# 3_6_1--esp32_-_0604.net
KiCad netlist of a schematic drawn in EasyEDA Pro
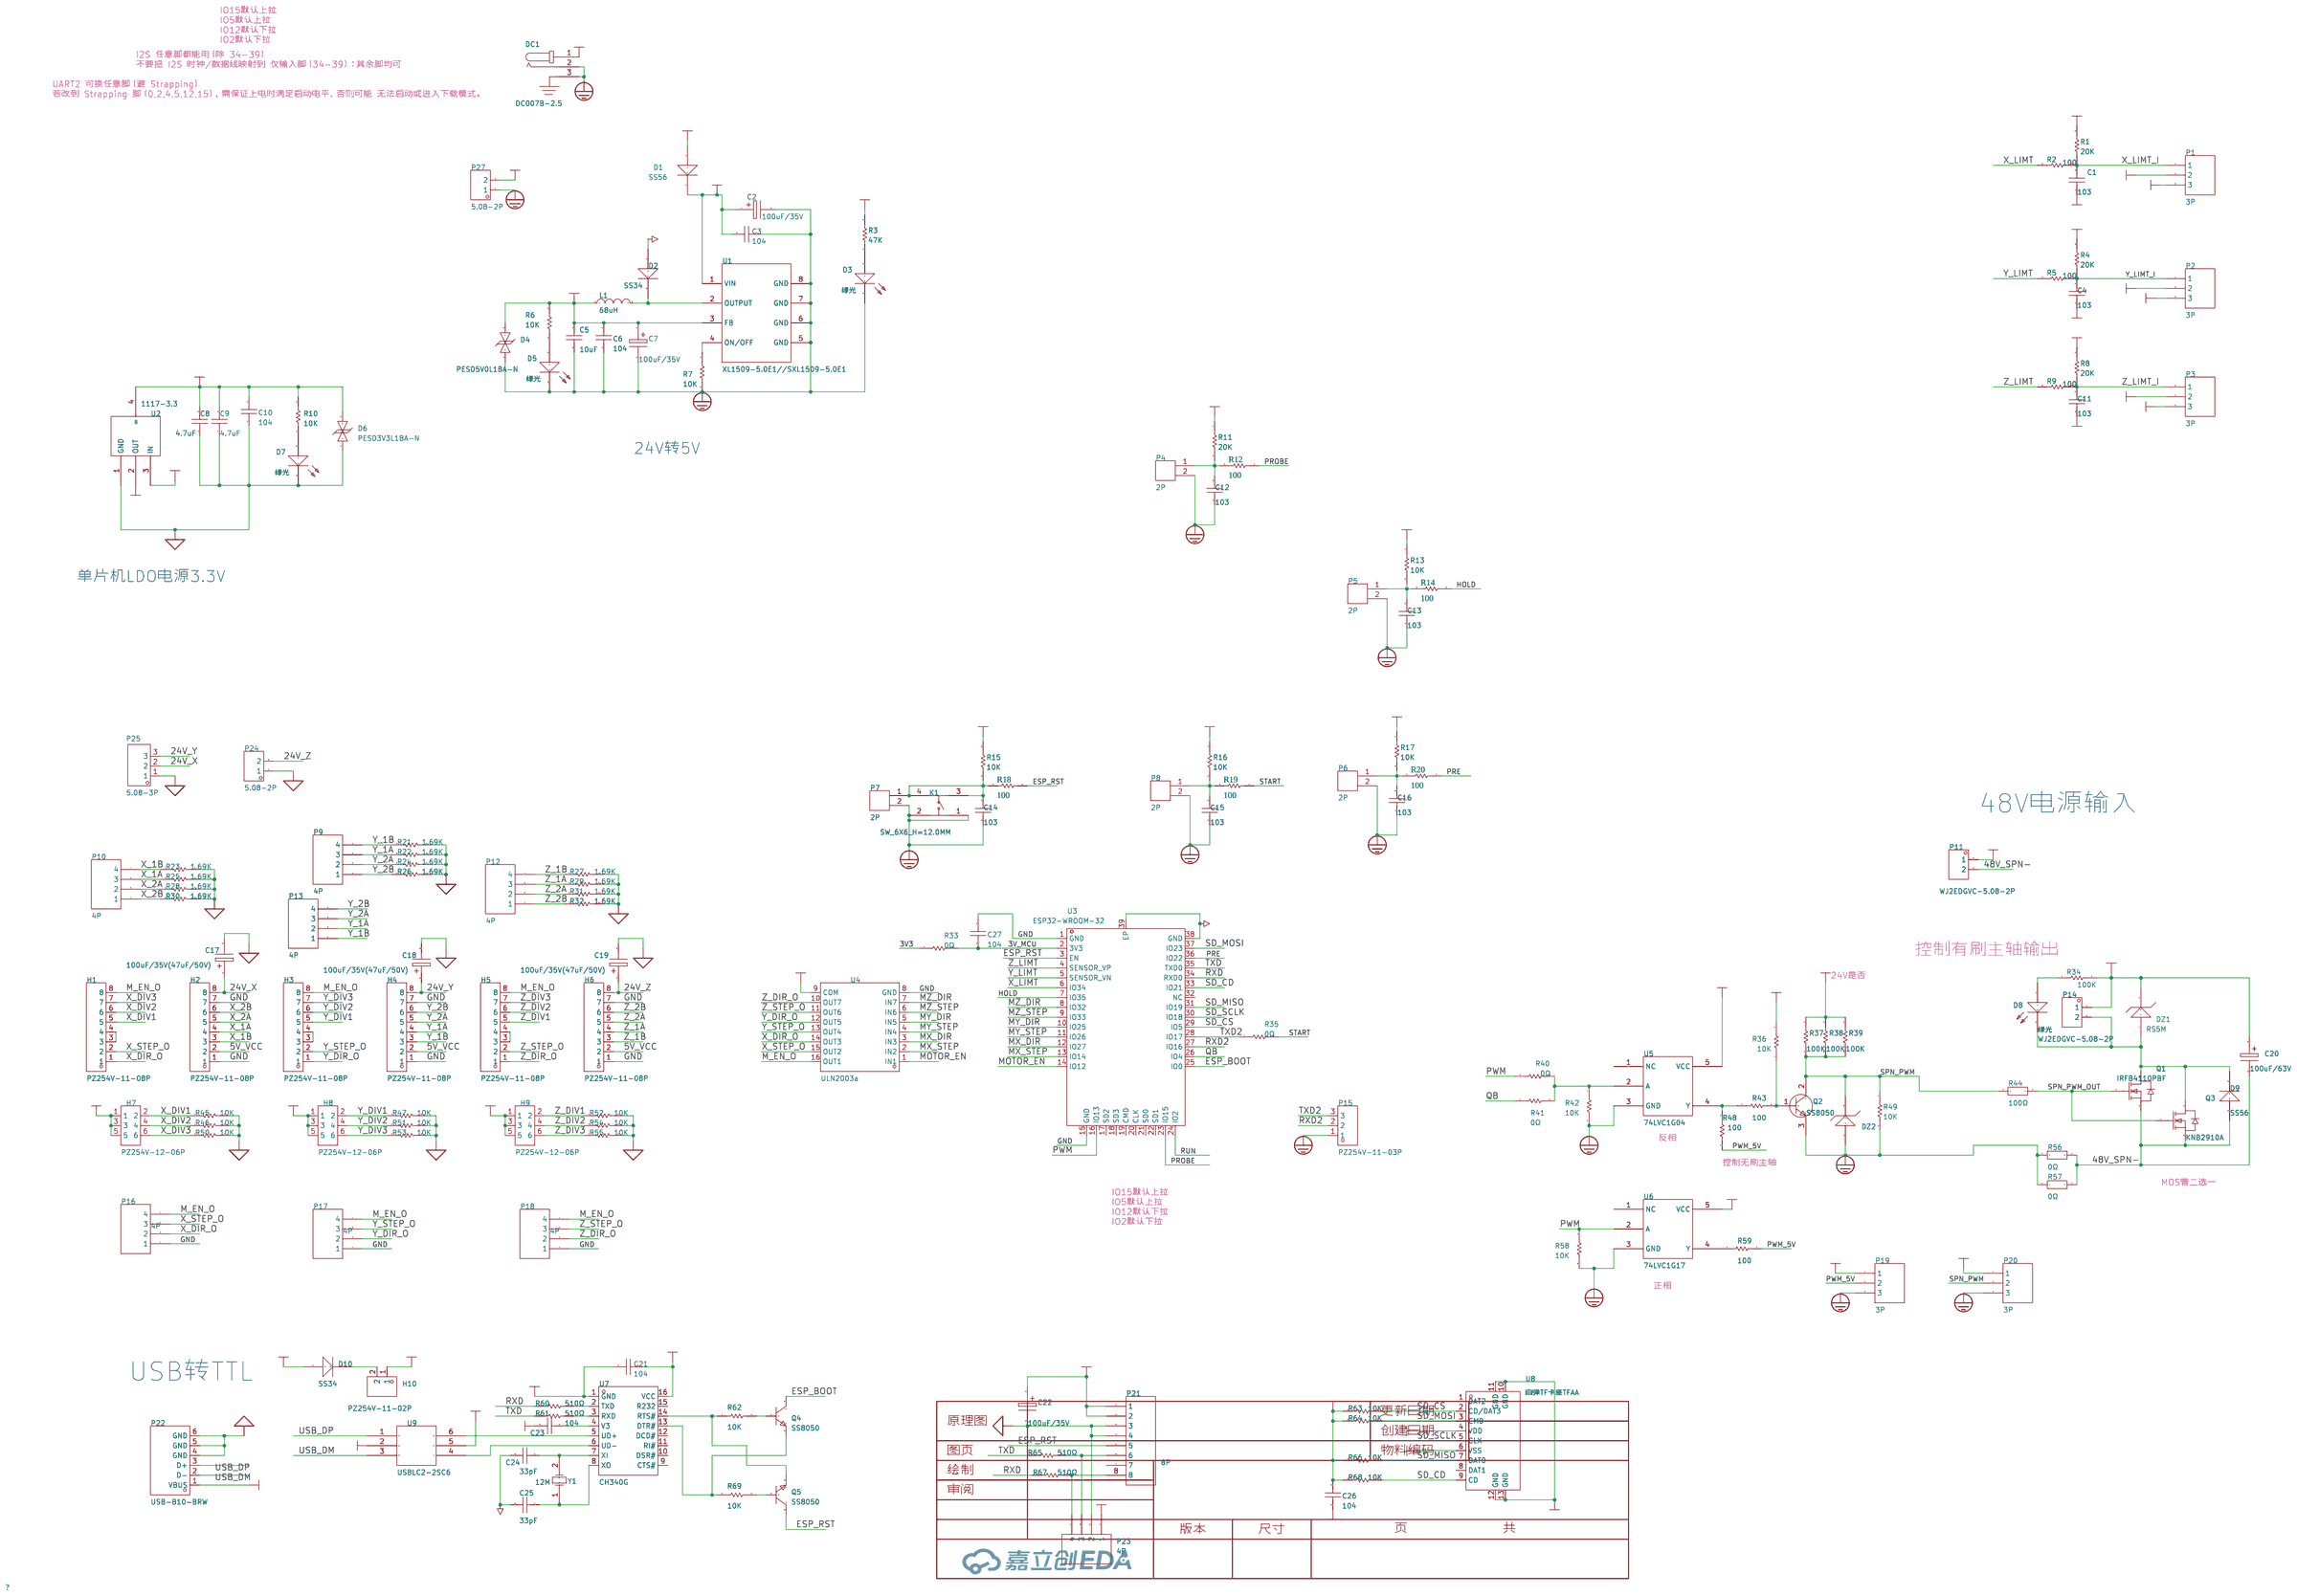
[diagram p0: schematic sheet]

(export (version "E")
  (design (tool "Eeschema 10.0.6"))
  (components
    (comp (ref "C1") (value "103") (footprint "easyedapro:11") (libsource (lib "easyedapro") (part "CAP")))
    (comp (ref "C2")
      (value "100uF/35V")
      (footprint "easyedapro:电解电容贴片10x10")
      (libsource (lib "easyedapro") (part "ELECTRO1"))
    )
    (comp (ref "C3")
      (value "104")
      (footprint "easyedapro:0603C")
      (description "Capacitor (Semiconductor SIM Model)")
      (libsource (lib "easyedapro") (part "Cap Semi"))
    )
    (comp (ref "C4") (value "103") (footprint "easyedapro:11") (libsource (lib "easyedapro") (part "CAP")))
    (comp (ref "C5") (value "10uF") (libsource (lib "") (part "CAP_1")))
    (comp (ref "C6")
      (value "104")
      (footprint "easyedapro:0603C")
      (description "Capacitor (Semiconductor SIM Model)")
      (libsource (lib "easyedapro") (part "Cap Semi"))
    )
    (comp (ref "C7")
      (value "100uF/35V")
      (footprint "easyedapro:0603C")
      (libsource (lib "easyedapro") (part "ELECTRO1"))
    )
    (comp (ref "C8") (value "4.7uF") (libsource (lib "") (part "CAP_1")))
    (comp (ref "C9") (value "4.7uF") (libsource (lib "") (part "CAP_1")))
    (comp (ref "C10")
      (value "104")
      (footprint "easyedapro:0603C")
      (description "Capacitor (Semiconductor SIM Model)")
      (libsource (lib "easyedapro") (part "Cap Semi"))
    )
    (comp (ref "C11") (value "103") (footprint "easyedapro:11") (libsource (lib "easyedapro") (part "CAP")))
    (comp (ref "C12") (value "103") (footprint "easyedapro:11") (libsource (lib "easyedapro") (part "CAP")))
    (comp (ref "C13") (value "103") (footprint "easyedapro:11") (libsource (lib "easyedapro") (part "CAP")))
    (comp (ref "C14") (value "103") (footprint "easyedapro:11") (libsource (lib "easyedapro") (part "CAP")))
    (comp (ref "C15") (value "103") (footprint "easyedapro:11") (libsource (lib "easyedapro") (part "CAP")))
    (comp (ref "C16") (value "103") (footprint "easyedapro:11") (libsource (lib "easyedapro") (part "CAP")))
    (comp (ref "C17")
      (value "100uF/35V(47uF/50V)")
      (footprint "easyedapro:电解电容贴片10x10")
      (libsource (lib "easyedapro") (part "ELECTRO1"))
    )
    (comp (ref "C18")
      (value "100uF/35V(47uF/50V)")
      (footprint "easyedapro:电解电容贴片10x10")
      (libsource (lib "easyedapro") (part "ELECTRO1"))
    )
    (comp (ref "C19")
      (value "100uF/35V(47uF/50V)")
      (footprint "easyedapro:电解电容贴片10x10")
      (libsource (lib "easyedapro") (part "ELECTRO1"))
    )
    (comp (ref "C20")
      (value "100uF/63V")
      (footprint "easyedapro:电解电容贴片10x10")
      (libsource (lib "easyedapro") (part "ELECTRO1"))
    )
    (comp (ref "C21")
      (value "104")
      (footprint "easyedapro:0603C")
      (description "Capacitor (Semiconductor SIM Model)")
      (libsource (lib "easyedapro") (part "Cap Semi"))
    )
    (comp (ref "C22")
      (value "100uF/35V")
      (footprint "easyedapro:电解电容贴片10x10")
      (libsource (lib "easyedapro") (part "ELECTRO1"))
    )
    (comp (ref "C23")
      (value "104")
      (footprint "easyedapro:0603C")
      (description "Capacitor (Semiconductor SIM Model)")
      (libsource (lib "easyedapro") (part "Cap Semi"))
    )
    (comp (ref "C24")
      (value "18pF")
      (footprint "easyedapro:0603C")
      (description "Capacitor (Semiconductor SIM Model)")
      (libsource (lib "easyedapro") (part "Cap Semi"))
    )
    (comp (ref "C25")
      (value "18pF")
      (footprint "easyedapro:0603C")
      (description "Capacitor (Semiconductor SIM Model)")
      (libsource (lib "easyedapro") (part "Cap Semi"))
    )
    (comp (ref "C26")
      (value "104")
      (footprint "easyedapro:11")
      (description "Capacitor (Semiconductor SIM Model)")
      (libsource (lib "easyedapro") (part "Cap Semi"))
    )
    (comp (ref "C27")
      (value "104")
      (footprint "easyedapro:0603C")
      (description "Capacitor (Semiconductor SIM Model)")
      (libsource (lib "easyedapro") (part "Cap Semi"))
    )
    (comp (ref "D1") (value "SS56") (footprint "easyedapro:SMA") (libsource (lib "") (part "1N4148_1")))
    (comp (ref "D2") (value "SS34") (libsource (lib "easyedapro") (part "1N4148")))
    (comp (ref "D3")
      (value "绿光")
      (footprint "easyedapro:0603LED")
      (libsource (lib "easyedapro") (part "LED"))
    )
    (comp (ref "D4")
      (value "PESD5V0L1BA-N")
      (footprint "easyedapro:SOD-523_L1.2-W0.8-LS1.6-BI")
      (description "极性:Bidirectional;反向关断电压（典型值）:5V (Max);击穿电压（最小值）:6V;箝位电压:15V;峰值脉冲电流（10/1000us）:5A (8/20us);")
      (fields (field (name "Manufacturer") "BORN伯恩半导体"))
      (libsource (lib "easyedapro") (part "PESD5V0S1BBN"))
    )
    (comp (ref "D5")
      (value "绿光")
      (footprint "easyedapro:0603LED")
      (libsource (lib "easyedapro") (part "LED"))
    )
    (comp (ref "D6")
      (value "PESD3V3L1BA-N")
      (footprint "easyedapro:SOD-523_L1.2-W0.8-LS1.6-BI")
      (description "极性:Bidirectional;反向关断电压（典型值）:5V (Max);击穿电压（最小值）:6V;箝位电压:15V;峰值脉冲电流（10/1000us）:5A (8/20us);")
      (fields (field (name "Manufacturer") "BORN伯恩半导体"))
      (libsource (lib "easyedapro") (part "PESD5V0S1BBN"))
    )
    (comp (ref "D7")
      (value "绿光")
      (footprint "easyedapro:0603LED")
      (libsource (lib "easyedapro") (part "LED"))
    )
    (comp (ref "D8")
      (value "绿光")
      (footprint "easyedapro:0603LED")
      (libsource (lib "easyedapro") (part "LED"))
    )
    (comp (ref "D9") (value "SS56") (libsource (lib "easyedapro") (part "1N4148")))
    (comp (ref "D10") (value "SS34") (footprint "easyedapro:SMA") (libsource (lib "") (part "1N4148_1")))
    (comp (ref "DC1")
      (value "DC007B-2.5")
      (footprint "easyedapro:DC-IN-TH_HX-DC007B-2.5")
      (description "连接器类型:DC电源插座;安装方式:弯插;触点内径:2.5mm;触点外径:7.7mm;额定电流:5A;额定电压:20V;工作温度:-25°C~+70°C;")
      (fields (field (name "Manufacturer") "SHOU HAN(首韩)"))
      (libsource (lib "easyedapro") (part "DC007B-2.5"))
    )
    (comp (ref "DZ1") (value "RS5M") (libsource (lib "easyedapro") (part "ѹ")))
    (comp (ref "DZ2") (value "--ѹ------SMAZ10V") (libsource (lib "easyedapro") (part "ѹ")))
    (comp (ref "H1")
      (value "PZ254V-11-08P")
      (footprint "easyedapro:HDR-TH_8P-P2.54-V-M")
      (fields (field (name "Manufacturer") "XFCN(兴飞)"))
      (libsource (lib "easyedapro") (part "PZ254V-11-08P"))
    )
    (comp (ref "H2")
      (value "PZ254V-11-08P")
      (footprint "easyedapro:HDR-TH_8P-P2.54-V-M")
      (fields (field (name "Manufacturer") "XFCN(兴飞)"))
      (libsource (lib "easyedapro") (part "PZ254V-11-08P"))
    )
    (comp (ref "H3")
      (value "PZ254V-11-08P")
      (footprint "easyedapro:HDR-TH_8P-P2.54-V-M")
      (fields (field (name "Manufacturer") "XFCN(兴飞)"))
      (libsource (lib "easyedapro") (part "PZ254V-11-08P"))
    )
    (comp (ref "H4")
      (value "PZ254V-11-08P")
      (footprint "easyedapro:HDR-TH_8P-P2.54-V-M")
      (fields (field (name "Manufacturer") "XFCN(兴飞)"))
      (libsource (lib "easyedapro") (part "PZ254V-11-08P"))
    )
    (comp (ref "H5")
      (value "PZ254V-11-08P")
      (footprint "easyedapro:HDR-TH_8P-P2.54-V-M")
      (fields (field (name "Manufacturer") "XFCN(兴飞)"))
      (libsource (lib "easyedapro") (part "PZ254V-11-08P"))
    )
    (comp (ref "H6")
      (value "PZ254V-11-08P")
      (footprint "easyedapro:HDR-TH_8P-P2.54-V-M")
      (fields (field (name "Manufacturer") "XFCN(兴飞)"))
      (libsource (lib "easyedapro") (part "PZ254V-11-08P"))
    )
    (comp (ref "H7")
      (value "PZ254V-12-06P")
      (footprint "easyedapro:HDR-TH_PZ254V-12-06P-A40")
      (description "排针2.54mm间距 直插 2x03位 直针外露4mm")
      (fields (field (name "Manufacturer") "XFCN(兴飞)"))
      (libsource (lib "easyedapro") (part "PZ254V-12-06P-A40"))
    )
    (comp (ref "H8")
      (value "PZ254V-12-06P")
      (footprint "easyedapro:HDR-TH_PZ254V-12-06P-A40")
      (description "排针2.54mm间距 直插 2x03位 直针外露4mm")
      (fields (field (name "Manufacturer") "XFCN(兴飞)"))
      (libsource (lib "easyedapro") (part "PZ254V-12-06P-A40"))
    )
    (comp (ref "H9")
      (value "PZ254V-12-06P")
      (footprint "easyedapro:HDR-TH_PZ254V-12-06P-A40")
      (description "排针2.54mm间距 直插 2x03位 直针外露4mm")
      (fields (field (name "Manufacturer") "XFCN(兴飞)"))
      (libsource (lib "easyedapro") (part "PZ254V-12-06P-A40"))
    )
    (comp (ref "H10")
      (value "PZ254V-11-02P")
      (footprint "easyedapro:HDR-TH_2P-P2.54-V-M")
      (fields (field (name "Manufacturer") "XFCN(兴飞)"))
      (libsource (lib "easyedapro") (part "PZ254V-11-02P"))
    )
    (comp (ref "K1")
      (value "SW_6X6_H=12.0MM")
      (footprint "easyedapro:KEY-SMD_4P-L6.0-W6.0-P4.50-LS9.0")
      (libsource (lib "easyedapro") (part "SW_6X6_H=12.0MM"))
    )
    (comp (ref "L1")
      (value "68uH")
      (footprint "easyedapro:IND-SMD_L7.0-W7.0_SMDRI74-330MT")
      (description "电感值:33uH;精度:±20%;额定电流:960mA;饱和电流(Isat):1.8A;类型:屏蔽电感;")
      (fields (field (name "Manufacturer Part") "SMDRI74-330MT") (field (name "Manufacturer") "SXN(顺翔诺)"))
      (libsource (lib "easyedapro") (part "SMDRI74-330MT"))
    )
    (comp (ref "P1")
      (value "3P")
      (footprint "easyedapro:HDR1X3_CON")
      (libsource (lib "easyedapro") (part "3P"))
    )
    (comp (ref "P2")
      (value "3P")
      (footprint "easyedapro:HDR1X3_CON")
      (libsource (lib "easyedapro") (part "3P"))
    )
    (comp (ref "P3")
      (value "3P")
      (footprint "easyedapro:HDR1X3_CON")
      (libsource (lib "easyedapro") (part "3P"))
    )
    (comp (ref "P4") (value "2P") (libsource (lib "easyedapro") (part "2P")))
    (comp (ref "P5") (value "2P") (libsource (lib "easyedapro") (part "2P")))
    (comp (ref "P6") (value "2P") (libsource (lib "easyedapro") (part "2P")))
    (comp (ref "P7") (value "2P") (libsource (lib "easyedapro") (part "2P")))
    (comp (ref "P8") (value "2P") (libsource (lib "easyedapro") (part "2P")))
    (comp (ref "P9") (value "4P") (footprint "easyedapro:HDR1X4_CON") (libsource (lib "") (part "4P_1")))
    (comp (ref "P10") (value "4P") (footprint "easyedapro:HDR1X4_CON") (libsource (lib "") (part "4P_1")))
    (comp (ref "P11")
      (value "WJ2EDGVC-5.08-2P")
      (footprint "easyedapro:CONN-TH_WJ2EDGVC-5.08-2P")
      (fields (field (name "Manufacturer") "KANGNEX(康奈克斯电气)"))
      (libsource (lib "easyedapro") (part "WJ2EDGVC-5.08-2P"))
    )
    (comp (ref "P12") (value "4P") (footprint "easyedapro:HDR1X4_CON") (libsource (lib "") (part "4P_1")))
    (comp (ref "P13") (value "4P") (footprint "easyedapro:HDR1X4_CON") (libsource (lib "") (part "4P_1")))
    (comp (ref "P14")
      (value "WJ2EDGVC-5.08-2P")
      (footprint "easyedapro:CONN-TH_WJ2EDGVC-5.08-2P")
      (fields (field (name "Manufacturer") "KANGNEX(康奈克斯电气)"))
      (libsource (lib "easyedapro") (part "WJ2EDGVC-5.08-2P"))
    )
    (comp (ref "P15")
      (value "PZ254V-11-03P")
      (footprint "easyedapro:HDR-TH_3P-P2.54-V-M")
      (fields (field (name "Manufacturer") "XFCN(兴飞)"))
      (libsource (lib "easyedapro") (part "PZ254V-11-03P_C2937625"))
    )
    (comp (ref "P16") (value "4P") (libsource (lib "easyedapro") (part "4P")))
    (comp (ref "P17") (value "4P") (libsource (lib "easyedapro") (part "4P")))
    (comp (ref "P18") (value "4P") (libsource (lib "easyedapro") (part "4P")))
    (comp (ref "P19")
      (value "3P")
      (footprint "easyedapro:HDR1X3_CON")
      (libsource (lib "easyedapro") (part "3P"))
    )
    (comp (ref "P20")
      (value "3P")
      (footprint "easyedapro:HDR1X3_CON")
      (libsource (lib "easyedapro") (part "3P"))
    )
    (comp (ref "P21") (value "8P") (footprint "easyedapro:IDC8") (libsource (lib "easyedapro") (part "8P")))
    (comp (ref "P22")
      (value "USB-B10-BRW")
      (footprint "easyedapro:USB-B-TH_USB-B10-BRW")
      (fields (field (name "Manufacturer") "XUNPU(讯普)"))
      (libsource (lib "easyedapro") (part "USB-B10-BRW"))
    )
    (comp (ref "P23") (value "4P") (footprint "easyedapro:HDR1X4_CON") (libsource (lib "") (part "4P_1")))
    (comp (ref "P24")
      (value "5.08-2P")
      (footprint "easyedapro:CONN-TH_WJ2EDGVC-5.08-2P")
      (fields (field (name "Manufacturer") "KANGNEX(康奈克斯电气)"))
      (libsource (lib "easyedapro") (part "WJ2EDGVC-5.08-2P"))
    )
    (comp (ref "P25")
      (value "5.08-3P")
      (footprint "easyedapro:CONN-TH_3P-P5.08-WJ2EDGVC-3P")
      (description "连接器类型:板端/插座-闭口;间距:5.08mm;排数:1;每排PIN数:3;安装方式:直针;颜色:绿色;")
      (fields (field (name "Manufacturer") "KANGNEX(康奈克斯电气)"))
      (libsource (lib "easyedapro") (part "WJ2EDGVC-3P"))
    )
    (comp (ref "P27")
      (value "5.08-2P")
      (footprint "easyedapro:CONN-TH_WJ2EDGVC-5.08-2P")
      (fields (field (name "Manufacturer") "KANGNEX(康奈克斯电气)"))
      (libsource (lib "easyedapro") (part "WJ2EDGVC-5.08-2P"))
    )
    (comp (ref "Q1")
      (value "IRFB4110PBF")
      (footprint "easyedapro:TO-220-3_L10.0-W4.5-P2.54-L")
      (fields (field (name "Manufacturer") "Infineon(英飞凌)"))
      (libsource (lib "easyedapro") (part "IRFB4110PBF"))
    )
    (comp (ref "Q2")
      (value "SS8050")
      (fields (field (name "Publisher") "Altium Limited"))
      (libsource (lib "easyedapro") (part "NPN"))
    )
    (comp (ref "Q3")
      (value "KNB2910A")
      (footprint "easyedapro:TO-263-2_L10.0-W9.1-P5.08-LS15.2-TL")
      (description "类型:-;漏源电压(Vdss):100V;连续漏极电流(Id):130A;导通电阻(RDS(on)):9mΩ@70V,10A;耗散功率(Pd):300W;阈值电压(Vgs(th)):4V;")
      (fields (field (name "Manufacturer") "KIA"))
      (libsource (lib "easyedapro") (part "KNB2910A"))
    )
    (comp (ref "Q4")
      (value "SS8050")
      (footprint "easyedapro:SOT-23-3_L2.9-W1.3-P1.90-LS2.4-BR")
      (fields (field (name "Manufacturer") "Doeshare(德芯)"))
      (libsource (lib "easyedapro") (part "SS8050_C2931717"))
    )
    (comp (ref "Q5")
      (value "SS8050")
      (footprint "easyedapro:SOT-23-3_L2.9-W1.3-P1.90-LS2.4-BR")
      (fields (field (name "Manufacturer") "Doeshare(德芯)"))
      (libsource (lib "easyedapro") (part "SS8050_C2931717"))
    )
    (comp (ref "R1")
      (value "20K")
      (footprint "easyedapro:10")
      (description "Resistor")
      (libsource (lib "easyedapro") (part "RES"))
    )
    (comp (ref "R2")
      (value "100")
      (footprint "easyedapro:10")
      (description "Resistor")
      (libsource (lib "easyedapro") (part "RES"))
    )
    (comp (ref "R3")
      (value "47K")
      (footprint "easyedapro:0603R")
      (description "Resistor")
      (libsource (lib "easyedapro") (part "RES"))
    )
    (comp (ref "R4")
      (value "20K")
      (footprint "easyedapro:10")
      (description "Resistor")
      (libsource (lib "easyedapro") (part "RES"))
    )
    (comp (ref "R5")
      (value "100")
      (footprint "easyedapro:10")
      (description "Resistor")
      (libsource (lib "easyedapro") (part "RES"))
    )
    (comp (ref "R6")
      (value "10K")
      (footprint "easyedapro:0603R")
      (description "Resistor")
      (libsource (lib "easyedapro") (part "RES"))
    )
    (comp (ref "R7")
      (value "10K")
      (footprint "easyedapro:0603R")
      (description "Resistor")
      (libsource (lib "easyedapro") (part "RES"))
    )
    (comp (ref "R8")
      (value "20K")
      (footprint "easyedapro:10")
      (description "Resistor")
      (libsource (lib "easyedapro") (part "RES"))
    )
    (comp (ref "R9")
      (value "100")
      (footprint "easyedapro:10")
      (description "Resistor")
      (libsource (lib "easyedapro") (part "RES"))
    )
    (comp (ref "R10")
      (value "10K")
      (footprint "easyedapro:0603R")
      (description "Resistor")
      (libsource (lib "easyedapro") (part "RES"))
    )
    (comp (ref "R11")
      (value "10K")
      (footprint "easyedapro:0603R")
      (description "Resistor")
      (libsource (lib "easyedapro") (part "RES"))
    )
    (comp (ref "R12")
      (value "100")
      (description "Resistor")
      (fields (field (name "Publisher") "Altium Limited"))
      (libsource (lib "") (part "RES_1"))
    )
    (comp (ref "R13")
      (value "10K")
      (footprint "easyedapro:0603R")
      (description "Resistor")
      (libsource (lib "easyedapro") (part "RES"))
    )
    (comp (ref "R14")
      (value "100")
      (description "Resistor")
      (fields (field (name "Publisher") "Altium Limited"))
      (libsource (lib "") (part "RES_1"))
    )
    (comp (ref "R15")
      (value "10K")
      (footprint "easyedapro:0603R")
      (description "Resistor")
      (libsource (lib "easyedapro") (part "RES"))
    )
    (comp (ref "R16")
      (value "10K")
      (footprint "easyedapro:0603R")
      (description "Resistor")
      (libsource (lib "easyedapro") (part "RES"))
    )
    (comp (ref "R17")
      (value "10K")
      (footprint "easyedapro:0603R")
      (description "Resistor")
      (libsource (lib "easyedapro") (part "RES"))
    )
    (comp (ref "R18")
      (value "100")
      (description "Resistor")
      (fields (field (name "Publisher") "Altium Limited"))
      (libsource (lib "") (part "RES_1"))
    )
    (comp (ref "R19")
      (value "100")
      (description "Resistor")
      (fields (field (name "Publisher") "Altium Limited"))
      (libsource (lib "") (part "RES_1"))
    )
    (comp (ref "R20")
      (value "100")
      (description "Resistor")
      (fields (field (name "Publisher") "Altium Limited"))
      (libsource (lib "") (part "RES_1"))
    )
    (comp (ref "R21")
      (value "10K")
      (footprint "easyedapro:0603R")
      (description "Resistor")
      (libsource (lib "easyedapro") (part "10K"))
    )
    (comp (ref "R22")
      (value "10K")
      (footprint "easyedapro:0603R")
      (description "Resistor")
      (libsource (lib "easyedapro") (part "10K"))
    )
    (comp (ref "R23")
      (value "10K")
      (footprint "easyedapro:0603R")
      (description "Resistor")
      (libsource (lib "easyedapro") (part "10K"))
    )
    (comp (ref "R24")
      (value "10K")
      (footprint "easyedapro:0603R")
      (description "Resistor")
      (libsource (lib "easyedapro") (part "10K"))
    )
    (comp (ref "R25")
      (value "10K")
      (footprint "easyedapro:0603R")
      (description "Resistor")
      (libsource (lib "easyedapro") (part "10K"))
    )
    (comp (ref "R26")
      (value "10K")
      (footprint "easyedapro:0603R")
      (description "Resistor")
      (libsource (lib "easyedapro") (part "10K"))
    )
    (comp (ref "R27")
      (value "10K")
      (footprint "easyedapro:0603R")
      (description "Resistor")
      (libsource (lib "easyedapro") (part "10K"))
    )
    (comp (ref "R28")
      (value "10K")
      (footprint "easyedapro:0603R")
      (description "Resistor")
      (libsource (lib "easyedapro") (part "10K"))
    )
    (comp (ref "R29")
      (value "10K")
      (footprint "easyedapro:0603R")
      (description "Resistor")
      (libsource (lib "easyedapro") (part "10K"))
    )
    (comp (ref "R30")
      (value "10K")
      (footprint "easyedapro:0603R")
      (description "Resistor")
      (libsource (lib "easyedapro") (part "10K"))
    )
    (comp (ref "R31")
      (value "10K")
      (footprint "easyedapro:0603R")
      (description "Resistor")
      (libsource (lib "easyedapro") (part "10K"))
    )
    (comp (ref "R32")
      (value "10K")
      (footprint "easyedapro:0603R")
      (description "Resistor")
      (libsource (lib "easyedapro") (part "10K"))
    )
    (comp (ref "R33")
      (value "0Ω")
      (description "Resistor")
      (fields (field (name "Publisher") "Altium Limited"))
      (libsource (lib "") (part "RES_1"))
    )
    (comp (ref "R34")
      (value "100K")
      (description "Resistor")
      (fields (field (name "Publisher") "Altium Limited"))
      (libsource (lib "") (part "RES_1"))
    )
    (comp (ref "R35")
      (value "0Ω")
      (description "Resistor")
      (fields (field (name "Publisher") "Altium Limited"))
      (libsource (lib "") (part "RES_1"))
    )
    (comp (ref "R36")
      (value "10K")
      (description "Resistor")
      (fields (field (name "Publisher") "Altium Limited"))
      (libsource (lib "") (part "RES_1"))
    )
    (comp (ref "R37")
      (value "100K")
      (description "Resistor")
      (fields (field (name "Publisher") "Altium Limited"))
      (libsource (lib "") (part "RES_1"))
    )
    (comp (ref "R38")
      (value "100K")
      (description "Resistor")
      (fields (field (name "Publisher") "Altium Limited"))
      (libsource (lib "") (part "RES_1"))
    )
    (comp (ref "R39")
      (value "100K")
      (description "Resistor")
      (fields (field (name "Publisher") "Altium Limited"))
      (libsource (lib "") (part "RES_1"))
    )
    (comp (ref "R40")
      (value "0Ω")
      (description "Resistor")
      (fields (field (name "Publisher") "Altium Limited"))
      (libsource (lib "") (part "RES_1"))
    )
    (comp (ref "R41")
      (value "0Ω")
      (description "Resistor")
      (fields (field (name "Publisher") "Altium Limited"))
      (libsource (lib "") (part "RES_1"))
    )
    (comp (ref "R42")
      (value "10K")
      (description "Resistor")
      (fields (field (name "Publisher") "Altium Limited"))
      (libsource (lib "") (part "RES_1"))
    )
    (comp (ref "R43")
      (value "100")
      (description "Resistor")
      (fields (field (name "Publisher") "Altium Limited"))
      (libsource (lib "") (part "RES_1"))
    )
    (comp (ref "R44")
      (value "100Ω")
      (footprint "easyedapro:R1210")
      (libsource (lib "easyedapro") (part "电阻"))
    )
    (comp (ref "R45")
      (value "10K")
      (footprint "easyedapro:0603R")
      (description "Resistor")
      (libsource (lib "easyedapro") (part "10K"))
    )
    (comp (ref "R46")
      (value "10K")
      (footprint "easyedapro:0603R")
      (description "Resistor")
      (libsource (lib "easyedapro") (part "10K"))
    )
    (comp (ref "R47")
      (value "10K")
      (footprint "easyedapro:0603R")
      (description "Resistor")
      (libsource (lib "easyedapro") (part "10K"))
    )
    (comp (ref "R48")
      (value "100")
      (description "Resistor")
      (fields (field (name "Publisher") "Altium Limited"))
      (libsource (lib "") (part "RES_1"))
    )
    (comp (ref "R49")
      (value "10K")
      (description "Resistor")
      (fields (field (name "Publisher") "Altium Limited"))
      (libsource (lib "") (part "RES_1"))
    )
    (comp (ref "R50")
      (value "10K")
      (footprint "easyedapro:0603R")
      (description "Resistor")
      (libsource (lib "easyedapro") (part "10K"))
    )
    (comp (ref "R51")
      (value "10K")
      (footprint "easyedapro:0603R")
      (description "Resistor")
      (libsource (lib "easyedapro") (part "10K"))
    )
    (comp (ref "R52")
      (value "10K")
      (footprint "easyedapro:0603R")
      (description "Resistor")
      (libsource (lib "easyedapro") (part "10K"))
    )
    (comp (ref "R53")
      (value "10K")
      (footprint "easyedapro:0603R")
      (description "Resistor")
      (libsource (lib "easyedapro") (part "10K"))
    )
    (comp (ref "R54")
      (value "10K")
      (footprint "easyedapro:0603R")
      (description "Resistor")
      (libsource (lib "easyedapro") (part "10K"))
    )
    (comp (ref "R55")
      (value "10K")
      (footprint "easyedapro:0603R")
      (description "Resistor")
      (libsource (lib "easyedapro") (part "10K"))
    )
    (comp (ref "R56") (value "0Ω") (footprint "easyedapro:R1210") (libsource (lib "easyedapro") (part "电阻")))
    (comp (ref "R57") (value "0Ω") (footprint "easyedapro:R1210") (libsource (lib "easyedapro") (part "电阻")))
    (comp (ref "R58")
      (value "10K")
      (description "Resistor")
      (fields (field (name "Publisher") "Altium Limited"))
      (libsource (lib "") (part "RES_1"))
    )
    (comp (ref "R59")
      (value "100")
      (description "Resistor")
      (fields (field (name "Publisher") "Altium Limited"))
      (libsource (lib "") (part "RES_1"))
    )
    (comp (ref "R60")
      (value "510Ω")
      (footprint "easyedapro:0603R")
      (description "Resistor")
      (libsource (lib "easyedapro") (part "RES"))
    )
    (comp (ref "R61")
      (value "510Ω")
      (footprint "easyedapro:0603R")
      (description "Resistor")
      (libsource (lib "easyedapro") (part "RES"))
    )
    (comp (ref "R62")
      (value "10K")
      (footprint "easyedapro:0603R")
      (description "Resistor")
      (libsource (lib "easyedapro") (part "RES"))
    )
    (comp (ref "R63")
      (value "10K")
      (footprint "easyedapro:10")
      (description "Resistor")
      (libsource (lib "easyedapro") (part "RES"))
    )
    (comp (ref "R64")
      (value "10K")
      (footprint "easyedapro:10")
      (description "Resistor")
      (libsource (lib "easyedapro") (part "RES"))
    )
    (comp (ref "R65")
      (value "510Ω")
      (footprint "easyedapro:0603R")
      (description "Resistor")
      (libsource (lib "easyedapro") (part "RES"))
    )
    (comp (ref "R66")
      (value "10K")
      (footprint "easyedapro:10")
      (description "Resistor")
      (libsource (lib "easyedapro") (part "RES"))
    )
    (comp (ref "R67")
      (value "510Ω")
      (footprint "easyedapro:0603R")
      (description "Resistor")
      (libsource (lib "easyedapro") (part "RES"))
    )
    (comp (ref "R68")
      (value "10K")
      (footprint "easyedapro:10")
      (description "Resistor")
      (libsource (lib "easyedapro") (part "RES"))
    )
    (comp (ref "R69")
      (value "10K")
      (footprint "easyedapro:0603R")
      (description "Resistor")
      (libsource (lib "easyedapro") (part "RES"))
    )
    (comp (ref "U1")
      (value "XL1509-5.0E1//SXL1509-5.0E1")
      (footprint "easyedapro:SOIC-8_L5.0-W4.0-P1.27-LS6.0-BL")
      (description "功能类型:降压型;同步整流:-;输出通道数:-;拓扑结构:-;输入电压:-;输出电流(最大值):-;开关频率:-;")
      (fields (field (name "Manufacturer") "XLSEMI(芯龙)"))
      (libsource (lib "easyedapro") (part "XL1509-5.0E1"))
    )
    (comp (ref "U2")
      (value "1117-3.3")
      (footprint "easyedapro:SOT-223")
      (libsource (lib "easyedapro") (part "LM1117"))
    )
    (comp (ref "U3")
      (value "ESP32-WROOM-32")
      (footprint "easyedapro:WIFIM-SMD_ESP-WROOM-32")
      (description "WiFi+双模蓝牙 双核CPU 网口 顶配MCU 低功耗蓝牙 ESP32系列ESP-WROOM-32模组/ESP-32S 4MB")
      (fields (field (name "Manufacturer") "ESPRESSIF(乐鑫)"))
      (libsource (lib "easyedapro") (part "ESP-WROOM-32"))
    )
    (comp (ref "U4")
      (value "ULN2003a")
      (footprint "easyedapro:SOP-16_L9.9-W3.9-P1.27-LS6.0-BL")
      (description "通道数:七路;集射击穿电压(Vceo):50V;集电极电流(Ic):500mA;")
      (fields (field (name "Manufacturer") "GR(国睿)"))
      (libsource (lib "easyedapro") (part "ULN2003_C18164408"))
    )
    (comp (ref "U5")
      (value "74LVC1G04")
      (footprint "easyedapro:SMD8")
      (libsource (lib "easyedapro") (part "74LVC1G04"))
    )
    (comp (ref "U6")
      (value "74LVC1G17")
      (footprint "easyedapro:SMD8")
      (libsource (lib "easyedapro") (part "74LVC1G04"))
    )
    (comp (ref "U7")
      (value "CH340G")
      (footprint "easyedapro:SOIC-16_L9.9-W3.9-P1.27-LS6.0-BL")
      (description "应用功能:收发器;接口协议:USB 2.0;数据速率:2Mbps;")
      (fields (field (name "Manufacturer") "WCH(南京沁恒)"))
      (libsource (lib "easyedapro") (part "CH340G"))
    )
    (comp (ref "U8")
      (value "自弹TF卡座TFAA")
      (footprint "easyedapro:SIM-SMD_C9900015645")
      (libsource (lib "easyedapro") (part "自弹TF卡座TFAA"))
    )
    (comp (ref "U9")
      (value "USBLC2-2SC6")
      (footprint "easyedapro:SOT-23-6")
      (libsource (lib "easyedapro") (part "DIP6"))
    )
    (comp (ref "Y1")
      (value "12M")
      (footprint "easyedapro:晶振贴片49SSMD")
      (description "Crystal Oscillator")
      (libsource (lib "easyedapro") (part "XTAL"))
    )
  )
  (nets
    (net (code "1") (name "/24V_X") (class "Default")
      (node (ref "C17") (pin "1") (pintype "unspecified"))
      (node (ref "H2") (pin "8") (pinfunction "8_8") (pintype "unspecified"))
      (node (ref "P25") (pin "2") (pinfunction "2_2") (pintype "input"))
    )
    (net (code "2") (name "/24V_Y") (class "Default")
      (node (ref "C18") (pin "1") (pintype "unspecified"))
      (node (ref "H4") (pin "8") (pinfunction "8_8") (pintype "unspecified"))
      (node (ref "P25") (pin "3") (pinfunction "3_3") (pintype "input"))
    )
    (net (code "3") (name "/24V_Z") (class "Default")
      (node (ref "C19") (pin "1") (pintype "unspecified"))
      (node (ref "H6") (pin "8") (pinfunction "8_8") (pintype "unspecified"))
      (node (ref "P24") (pin "2") (pinfunction "2_2") (pintype "unspecified"))
    )
    (net (code "4") (name "/48V_SPN-") (class "Default")
      (node (ref "C20") (pin "2") (pintype "unspecified"))
      (node (ref "D9") (pin "1") (pinfunction "1_1") (pintype "input"))
      (node (ref "P11") (pin "2") (pinfunction "2_2") (pintype "unspecified"))
      (node (ref "Q1") (pin "3") (pinfunction "S_3") (pintype "unspecified"))
      (node (ref "Q3") (pin "3") (pinfunction "S_3") (pintype "unspecified"))
      (node (ref "R56") (pin "2") (pinfunction "2_2") (pintype "input"))
      (node (ref "R57") (pin "2") (pinfunction "2_2") (pintype "input"))
    )
    (net (code "5") (name "/ESP_BOOT") (class "Default")
      (node (ref "Q4") (pin "3") (pinfunction "C_3") (pintype "unspecified"))
      (node (ref "U3") (pin "25") (pinfunction "IO0_25") (pintype "unspecified"))
    )
    (net (code "6") (name "/ESP_RST") (class "Default")
      (node (ref "P21") (pin "5") (pinfunction "5_5") (pintype "unspecified"))
      (node (ref "Q5") (pin "3") (pinfunction "C_3") (pintype "unspecified"))
      (node (ref "R18") (pin "1") (pinfunction "1_1") (pintype "input"))
      (node (ref "U3") (pin "3") (pinfunction "EN_3") (pintype "unspecified"))
    )
    (net (code "7") (name "/HOLD") (class "Default")
      (node (ref "R14") (pin "1") (pinfunction "1_1") (pintype "input"))
      (node (ref "U3") (pin "7") (pinfunction "IO35_7") (pintype "unspecified"))
    )
    (net (code "8") (name "/MOTOR_EN") (class "Default")
      (node (ref "U3") (pin "14") (pinfunction "IO12_14") (pintype "unspecified"))
      (node (ref "U4") (pin "1") (pinfunction "IN1_1") (pintype "unspecified"))
    )
    (net (code "9") (name "/MX_DIR") (class "Default")
      (node (ref "U3") (pin "12") (pinfunction "IO27_12") (pintype "unspecified"))
      (node (ref "U4") (pin "3") (pinfunction "IN3_3") (pintype "unspecified"))
    )
    (net (code "10") (name "/MX_STEP") (class "Default")
      (node (ref "U3") (pin "13") (pinfunction "IO14_13") (pintype "unspecified"))
      (node (ref "U4") (pin "2") (pinfunction "IN2_2") (pintype "unspecified"))
    )
    (net (code "11") (name "/MY_DIR") (class "Default")
      (node (ref "U3") (pin "10") (pinfunction "IO25_10") (pintype "unspecified"))
      (node (ref "U4") (pin "5") (pinfunction "IN5_5") (pintype "unspecified"))
    )
    (net (code "12") (name "/MY_STEP") (class "Default")
      (node (ref "U3") (pin "11") (pinfunction "IO26_11") (pintype "unspecified"))
      (node (ref "U4") (pin "4") (pinfunction "IN4_4") (pintype "unspecified"))
    )
    (net (code "13") (name "/MZ_DIR") (class "Default")
      (node (ref "U3") (pin "8") (pinfunction "IO32_8") (pintype "unspecified"))
      (node (ref "U4") (pin "7") (pinfunction "IN7_7") (pintype "unspecified"))
    )
    (net (code "14") (name "/MZ_STEP") (class "Default")
      (node (ref "U3") (pin "9") (pinfunction "IO33_9") (pintype "unspecified"))
      (node (ref "U4") (pin "6") (pinfunction "IN6_6") (pintype "unspecified"))
    )
    (net (code "15") (name "/M_EN_O") (class "Default")
      (node (ref "H1") (pin "8") (pinfunction "8_8") (pintype "unspecified"))
      (node (ref "H3") (pin "8") (pinfunction "8_8") (pintype "unspecified"))
      (node (ref "H5") (pin "8") (pinfunction "8_8") (pintype "unspecified"))
      (node (ref "P16") (pin "4") (pinfunction "4_4") (pintype "input"))
      (node (ref "P17") (pin "4") (pinfunction "4_4") (pintype "input"))
      (node (ref "P18") (pin "4") (pinfunction "4_4") (pintype "input"))
      (node (ref "U4") (pin "16") (pinfunction "OUT1_16") (pintype "unspecified"))
    )
    (net (code "16") (name "/PRE") (class "Default")
      (node (ref "R20") (pin "1") (pinfunction "1_1") (pintype "input"))
      (node (ref "U3") (pin "36") (pinfunction "IO22_36") (pintype "unspecified"))
    )
    (net (code "17") (name "/PROBE") (class "Default")
      (node (ref "R12") (pin "1") (pinfunction "1_1") (pintype "input"))
      (node (ref "U3") (pin "23") (pinfunction "IO15_23") (pintype "unspecified"))
    )
    (net (code "18") (name "/PWM") (class "Default")
      (node (ref "R40") (pin "1") (pinfunction "1_1") (pintype "input"))
      (node (ref "R58") (pin "1") (pinfunction "1_1") (pintype "input"))
      (node (ref "U3") (pin "16") (pinfunction "IO13_16") (pintype "unspecified"))
      (node (ref "U6") (pin "2") (pinfunction "A_2") (pintype "unspecified"))
    )
    (net (code "19") (name "/PWM_5V") (class "Default")
      (node (ref "P19") (pin "2") (pinfunction "2_2") (pintype "unspecified"))
      (node (ref "R48") (pin "1") (pinfunction "1_1") (pintype "input"))
      (node (ref "R59") (pin "2") (pinfunction "2_2") (pintype "input"))
    )
    (net (code "20") (name "/QB") (class "Default")
      (node (ref "R41") (pin "1") (pinfunction "1_1") (pintype "input"))
      (node (ref "U3") (pin "26") (pinfunction "IO4_26") (pintype "unspecified"))
    )
    (net (code "21") (name "/RUN") (class "Default")
      (node (ref "U3") (pin "24") (pinfunction "IO2_24") (pintype "unspecified"))
    )
    (net (code "22") (name "/RXD") (class "Default")
      (node (ref "R60") (pin "2") (pinfunction "2_2") (pintype "unspecified"))
      (node (ref "R67") (pin "1") (pinfunction "1_1") (pintype "unspecified"))
      (node (ref "U3") (pin "34") (pinfunction "RXD0_34") (pintype "unspecified"))
    )
    (net (code "23") (name "/RXD2") (class "Default")
      (node (ref "P15") (pin "2") (pinfunction "2_2") (pintype "unspecified"))
      (node (ref "U3") (pin "27") (pinfunction "IO16_27") (pintype "unspecified"))
    )
    (net (code "24") (name "/SD_CD") (class "Default")
      (node (ref "R68") (pin "1") (pinfunction "1_1") (pintype "unspecified"))
      (node (ref "U3") (pin "33") (pinfunction "IO21_33") (pintype "unspecified"))
      (node (ref "U8") (pin "9") (pinfunction "CD_9") (pintype "unspecified"))
    )
    (net (code "25") (name "/SD_CS") (class "Default")
      (node (ref "R63") (pin "1") (pinfunction "1_1") (pintype "unspecified"))
      (node (ref "U3") (pin "29") (pinfunction "IO5_29") (pintype "unspecified"))
      (node (ref "U8") (pin "2") (pinfunction "CD/DAT3_2") (pintype "unspecified"))
    )
    (net (code "26") (name "/SD_MISO") (class "Default")
      (node (ref "R66") (pin "1") (pinfunction "1_1") (pintype "unspecified"))
      (node (ref "U3") (pin "31") (pinfunction "IO19_31") (pintype "unspecified"))
      (node (ref "U8") (pin "7") (pinfunction "DAT0_7") (pintype "unspecified"))
    )
    (net (code "27") (name "/SD_MOSI") (class "Default")
      (node (ref "R64") (pin "1") (pinfunction "1_1") (pintype "unspecified"))
      (node (ref "U3") (pin "37") (pinfunction "IO23_37") (pintype "unspecified"))
      (node (ref "U8") (pin "3") (pinfunction "CMD_3") (pintype "unspecified"))
    )
    (net (code "28") (name "/SD_SCLK") (class "Default")
      (node (ref "U3") (pin "30") (pinfunction "IO18_30") (pintype "unspecified"))
      (node (ref "U8") (pin "5") (pinfunction "CLX_5") (pintype "unspecified"))
    )
    (net (code "29") (name "/SPN_PWM") (class "Default")
      (node (ref "DZ2") (pin "2") (pinfunction "2_2") (pintype "input"))
      (node (ref "P20") (pin "2") (pinfunction "2_2") (pintype "unspecified"))
      (node (ref "Q2") (pin "2") (pinfunction "C_2") (pintype "input"))
      (node (ref "R37") (pin "1") (pinfunction "1_1") (pintype "input"))
      (node (ref "R38") (pin "1") (pinfunction "1_1") (pintype "input"))
      (node (ref "R39") (pin "1") (pinfunction "1_1") (pintype "input"))
      (node (ref "R44") (pin "1") (pinfunction "1_1") (pintype "input"))
      (node (ref "R49") (pin "1") (pinfunction "1_1") (pintype "input"))
    )
    (net (code "30") (name "/SPN_PWM_OUT") (class "Default")
      (node (ref "Q1") (pin "1") (pinfunction "G_1") (pintype "unspecified"))
      (node (ref "Q3") (pin "1") (pinfunction "G_1") (pintype "unspecified"))
      (node (ref "R44") (pin "2") (pinfunction "2_2") (pintype "input"))
    )
    (net (code "31") (name "/START") (class "Default")
      (node (ref "R19") (pin "1") (pinfunction "1_1") (pintype "input"))
      (node (ref "R35") (pin "2") (pinfunction "2_2") (pintype "input"))
    )
    (net (code "32") (name "/TXD") (class "Default")
      (node (ref "R61") (pin "2") (pinfunction "2_2") (pintype "unspecified"))
      (node (ref "R65") (pin "1") (pinfunction "1_1") (pintype "unspecified"))
      (node (ref "U3") (pin "35") (pinfunction "TXD0_35") (pintype "unspecified"))
    )
    (net (code "33") (name "/TXD2") (class "Default")
      (node (ref "P15") (pin "3") (pinfunction "3_3") (pintype "unspecified"))
      (node (ref "R35") (pin "1") (pinfunction "1_1") (pintype "input"))
      (node (ref "U3") (pin "28") (pinfunction "IO17_28") (pintype "unspecified"))
    )
    (net (code "34") (name "/USB_DM") (class "Default")
      (node (ref "P22") (pin "2") (pinfunction "D-_2") (pintype "unspecified"))
      (node (ref "U9") (pin "3") (pinfunction "3_3") (pintype "unspecified"))
    )
    (net (code "35") (name "/USB_DP") (class "Default")
      (node (ref "P22") (pin "3") (pinfunction "D+_3") (pintype "unspecified"))
      (node (ref "U9") (pin "1") (pinfunction "1_1") (pintype "unspecified"))
    )
    (net (code "36") (name "/X_1A") (class "Default")
      (node (ref "H2") (pin "4") (pinfunction "4_4") (pintype "unspecified"))
      (node (ref "P10") (pin "3") (pinfunction "3_3") (pintype "unspecified"))
      (node (ref "R25") (pin "1") (pinfunction "1_1") (pintype "unspecified"))
    )
    (net (code "37") (name "/X_1B") (class "Default")
      (node (ref "H2") (pin "3") (pinfunction "3_3") (pintype "unspecified"))
      (node (ref "P10") (pin "4") (pinfunction "4_4") (pintype "unspecified"))
      (node (ref "R23") (pin "1") (pinfunction "1_1") (pintype "unspecified"))
    )
    (net (code "38") (name "/X_2A") (class "Default")
      (node (ref "H2") (pin "5") (pinfunction "5_5") (pintype "unspecified"))
      (node (ref "P10") (pin "2") (pinfunction "2_2") (pintype "unspecified"))
      (node (ref "R28") (pin "1") (pinfunction "1_1") (pintype "unspecified"))
    )
    (net (code "39") (name "/X_2B") (class "Default")
      (node (ref "H2") (pin "6") (pinfunction "6_6") (pintype "unspecified"))
      (node (ref "P10") (pin "1") (pinfunction "1_1") (pintype "unspecified"))
      (node (ref "R30") (pin "1") (pinfunction "1_1") (pintype "unspecified"))
    )
    (net (code "40") (name "/X_DIR_O") (class "Default")
      (node (ref "H1") (pin "1") (pinfunction "1_1") (pintype "unspecified"))
      (node (ref "P16") (pin "2") (pinfunction "2_2") (pintype "input"))
      (node (ref "U4") (pin "14") (pinfunction "OUT3_14") (pintype "unspecified"))
    )
    (net (code "41") (name "/X_DIV1") (class "Default")
      (node (ref "H1") (pin "5") (pinfunction "5_5") (pintype "unspecified"))
      (node (ref "H7") (pin "2") (pinfunction "2_2") (pintype "unspecified"))
      (node (ref "R45") (pin "1") (pinfunction "1_1") (pintype "unspecified"))
    )
    (net (code "42") (name "/X_DIV2") (class "Default")
      (node (ref "H1") (pin "6") (pinfunction "6_6") (pintype "unspecified"))
      (node (ref "H7") (pin "4") (pinfunction "4_4") (pintype "unspecified"))
      (node (ref "R46") (pin "1") (pinfunction "1_1") (pintype "unspecified"))
    )
    (net (code "43") (name "/X_DIV3") (class "Default")
      (node (ref "H1") (pin "7") (pinfunction "7_7") (pintype "unspecified"))
      (node (ref "H7") (pin "6") (pinfunction "6_6") (pintype "unspecified"))
      (node (ref "R50") (pin "1") (pinfunction "1_1") (pintype "unspecified"))
    )
    (net (code "44") (name "/X_LIMT") (class "Default")
      (node (ref "R2") (pin "2") (pinfunction "2_2") (pintype "unspecified"))
      (node (ref "U3") (pin "6") (pinfunction "IO34_6") (pintype "unspecified"))
    )
    (net (code "45") (name "/X_LIMT_I") (class "Default")
      (node (ref "C1") (pin "2") (pinfunction "2_2") (pintype "unspecified"))
      (node (ref "P1") (pin "1") (pinfunction "1_1") (pintype "unspecified"))
      (node (ref "R1") (pin "1") (pinfunction "1_1") (pintype "unspecified"))
      (node (ref "R2") (pin "1") (pinfunction "1_1") (pintype "unspecified"))
    )
    (net (code "46") (name "/X_STEP_O") (class "Default")
      (node (ref "H1") (pin "2") (pinfunction "2_2") (pintype "unspecified"))
      (node (ref "P16") (pin "3") (pinfunction "3_3") (pintype "input"))
      (node (ref "U4") (pin "15") (pinfunction "OUT2_15") (pintype "unspecified"))
    )
    (net (code "47") (name "/Y_1A") (class "Default")
      (node (ref "H4") (pin "4") (pinfunction "4_4") (pintype "unspecified"))
      (node (ref "P13") (pin "2") (pinfunction "2_2") (pintype "unspecified"))
      (node (ref "P9") (pin "3") (pinfunction "3_3") (pintype "unspecified"))
      (node (ref "R22") (pin "1") (pinfunction "1_1") (pintype "unspecified"))
    )
    (net (code "48") (name "/Y_1B") (class "Default")
      (node (ref "H4") (pin "3") (pinfunction "3_3") (pintype "unspecified"))
      (node (ref "P13") (pin "1") (pinfunction "1_1") (pintype "unspecified"))
      (node (ref "P9") (pin "4") (pinfunction "4_4") (pintype "unspecified"))
      (node (ref "R21") (pin "1") (pinfunction "1_1") (pintype "unspecified"))
    )
    (net (code "49") (name "/Y_2A") (class "Default")
      (node (ref "H4") (pin "5") (pinfunction "5_5") (pintype "unspecified"))
      (node (ref "P13") (pin "3") (pinfunction "3_3") (pintype "unspecified"))
      (node (ref "P9") (pin "2") (pinfunction "2_2") (pintype "unspecified"))
      (node (ref "R24") (pin "1") (pinfunction "1_1") (pintype "unspecified"))
    )
    (net (code "50") (name "/Y_2B") (class "Default")
      (node (ref "H4") (pin "6") (pinfunction "6_6") (pintype "unspecified"))
      (node (ref "P13") (pin "4") (pinfunction "4_4") (pintype "unspecified"))
      (node (ref "P9") (pin "1") (pinfunction "1_1") (pintype "unspecified"))
      (node (ref "R26") (pin "1") (pinfunction "1_1") (pintype "unspecified"))
    )
    (net (code "51") (name "/Y_DIR_O") (class "Default")
      (node (ref "H3") (pin "1") (pinfunction "1_1") (pintype "unspecified"))
      (node (ref "P17") (pin "2") (pinfunction "2_2") (pintype "input"))
      (node (ref "U4") (pin "12") (pinfunction "OUT5_12") (pintype "unspecified"))
    )
    (net (code "52") (name "/Y_DIV1") (class "Default")
      (node (ref "H3") (pin "5") (pinfunction "5_5") (pintype "unspecified"))
      (node (ref "H8") (pin "2") (pinfunction "2_2") (pintype "unspecified"))
      (node (ref "R47") (pin "1") (pinfunction "1_1") (pintype "unspecified"))
    )
    (net (code "53") (name "/Y_DIV2") (class "Default")
      (node (ref "H3") (pin "6") (pinfunction "6_6") (pintype "unspecified"))
      (node (ref "H8") (pin "4") (pinfunction "4_4") (pintype "unspecified"))
      (node (ref "R51") (pin "1") (pinfunction "1_1") (pintype "unspecified"))
    )
    (net (code "54") (name "/Y_DIV3") (class "Default")
      (node (ref "H3") (pin "7") (pinfunction "7_7") (pintype "unspecified"))
      (node (ref "H8") (pin "6") (pinfunction "6_6") (pintype "unspecified"))
      (node (ref "R53") (pin "1") (pinfunction "1_1") (pintype "unspecified"))
    )
    (net (code "55") (name "/Y_LIMT") (class "Default")
      (node (ref "R5") (pin "2") (pinfunction "2_2") (pintype "unspecified"))
      (node (ref "U3") (pin "5") (pinfunction "SENSOR_VN_5") (pintype "unspecified"))
    )
    (net (code "56") (name "/Y_LIMT_I") (class "Default")
      (node (ref "C4") (pin "2") (pinfunction "2_2") (pintype "unspecified"))
      (node (ref "P2") (pin "1") (pinfunction "1_1") (pintype "unspecified"))
      (node (ref "R4") (pin "1") (pinfunction "1_1") (pintype "unspecified"))
      (node (ref "R5") (pin "1") (pinfunction "1_1") (pintype "unspecified"))
    )
    (net (code "57") (name "/Y_STEP_O") (class "Default")
      (node (ref "H3") (pin "2") (pinfunction "2_2") (pintype "unspecified"))
      (node (ref "P17") (pin "3") (pinfunction "3_3") (pintype "input"))
      (node (ref "U4") (pin "13") (pinfunction "OUT4_13") (pintype "unspecified"))
    )
    (net (code "58") (name "/Z_1A") (class "Default")
      (node (ref "H6") (pin "4") (pinfunction "4_4") (pintype "unspecified"))
      (node (ref "P12") (pin "3") (pinfunction "3_3") (pintype "unspecified"))
      (node (ref "R29") (pin "1") (pinfunction "1_1") (pintype "unspecified"))
    )
    (net (code "59") (name "/Z_1B") (class "Default")
      (node (ref "H6") (pin "3") (pinfunction "3_3") (pintype "unspecified"))
      (node (ref "P12") (pin "4") (pinfunction "4_4") (pintype "unspecified"))
      (node (ref "R27") (pin "1") (pinfunction "1_1") (pintype "unspecified"))
    )
    (net (code "60") (name "/Z_2A") (class "Default")
      (node (ref "H6") (pin "5") (pinfunction "5_5") (pintype "unspecified"))
      (node (ref "P12") (pin "2") (pinfunction "2_2") (pintype "unspecified"))
      (node (ref "R31") (pin "1") (pinfunction "1_1") (pintype "unspecified"))
    )
    (net (code "61") (name "/Z_2B") (class "Default")
      (node (ref "H6") (pin "6") (pinfunction "6_6") (pintype "unspecified"))
      (node (ref "P12") (pin "1") (pinfunction "1_1") (pintype "unspecified"))
      (node (ref "R32") (pin "1") (pinfunction "1_1") (pintype "unspecified"))
    )
    (net (code "62") (name "/Z_DIR_O") (class "Default")
      (node (ref "H5") (pin "1") (pinfunction "1_1") (pintype "unspecified"))
      (node (ref "P18") (pin "2") (pinfunction "2_2") (pintype "input"))
      (node (ref "U4") (pin "10") (pinfunction "OUT7_10") (pintype "unspecified"))
    )
    (net (code "63") (name "/Z_DIV1") (class "Default")
      (node (ref "H5") (pin "5") (pinfunction "5_5") (pintype "unspecified"))
      (node (ref "H9") (pin "2") (pinfunction "2_2") (pintype "unspecified"))
      (node (ref "R52") (pin "1") (pinfunction "1_1") (pintype "unspecified"))
    )
    (net (code "64") (name "/Z_DIV2") (class "Default")
      (node (ref "H5") (pin "6") (pinfunction "6_6") (pintype "unspecified"))
      (node (ref "H9") (pin "4") (pinfunction "4_4") (pintype "unspecified"))
      (node (ref "R54") (pin "1") (pinfunction "1_1") (pintype "unspecified"))
    )
    (net (code "65") (name "/Z_DIV3") (class "Default")
      (node (ref "H5") (pin "7") (pinfunction "7_7") (pintype "unspecified"))
      (node (ref "H9") (pin "6") (pinfunction "6_6") (pintype "unspecified"))
      (node (ref "R55") (pin "1") (pinfunction "1_1") (pintype "unspecified"))
    )
    (net (code "66") (name "/Z_LIMT") (class "Default")
      (node (ref "R9") (pin "2") (pinfunction "2_2") (pintype "unspecified"))
      (node (ref "U3") (pin "4") (pinfunction "SENSOR_VP_4") (pintype "unspecified"))
    )
    (net (code "67") (name "/Z_LIMT_I") (class "Default")
      (node (ref "C11") (pin "2") (pinfunction "2_2") (pintype "unspecified"))
      (node (ref "P3") (pin "1") (pinfunction "1_1") (pintype "unspecified"))
      (node (ref "R8") (pin "1") (pinfunction "1_1") (pintype "unspecified"))
      (node (ref "R9") (pin "1") (pinfunction "1_1") (pintype "unspecified"))
    )
    (net (code "68") (name "/Z_STEP_O") (class "Default")
      (node (ref "H5") (pin "2") (pinfunction "2_2") (pintype "unspecified"))
      (node (ref "P18") (pin "3") (pinfunction "3_3") (pintype "input"))
      (node (ref "U4") (pin "11") (pinfunction "OUT6_11") (pintype "unspecified"))
    )
    (net (code "69") (name "3V3") (class "Default")
      (node (ref "C10") (pin "2") (pinfunction "2_2") (pintype "unspecified"))
      (node (ref "C26") (pin "2") (pinfunction "2_2") (pintype "unspecified"))
      (node (ref "C8") (pin "2") (pinfunction "2_2") (pintype "input"))
      (node (ref "C9") (pin "2") (pinfunction "2_2") (pintype "input"))
      (node (ref "D6") (pin "2") (pinfunction "2_2") (pintype "input"))
      (node (ref "R10") (pin "2") (pinfunction "2_2") (pintype "unspecified"))
      (node (ref "R13") (pin "1") (pinfunction "1_1") (pintype "unspecified"))
      (node (ref "R15") (pin "1") (pinfunction "1_1") (pintype "unspecified"))
      (node (ref "R33") (pin "1") (pinfunction "1_1") (pintype "input"))
      (node (ref "R63") (pin "2") (pinfunction "2_2") (pintype "unspecified"))
      (node (ref "R64") (pin "2") (pinfunction "2_2") (pintype "unspecified"))
      (node (ref "R66") (pin "2") (pinfunction "2_2") (pintype "unspecified"))
      (node (ref "R68") (pin "2") (pinfunction "2_2") (pintype "unspecified"))
      (node (ref "U2") (pin "2") (pinfunction "OUT_2") (pintype "unspecified"))
      (node (ref "U2") (pin "4") (pinfunction "=_4") (pintype "unspecified"))
      (node (ref "U8") (pin "4") (pinfunction "VDD_4") (pintype "unspecified"))
    )
    (net (code "70") (name "3V_MCU") (class "Default")
      (node (ref "C27") (pin "1") (pinfunction "1_1") (pintype "unspecified"))
      (node (ref "R16") (pin "1") (pinfunction "1_1") (pintype "unspecified"))
      (node (ref "R17") (pin "1") (pinfunction "1_1") (pintype "unspecified"))
      (node (ref "R33") (pin "2") (pinfunction "2_2") (pintype "input"))
      (node (ref "U3") (pin "2") (pinfunction "3V3_2") (pintype "unspecified"))
    )
    (net (code "71") (name "5V_VCC") (class "Default")
      (node (ref "C21") (pin "1") (pinfunction "1_1") (pintype "unspecified"))
      (node (ref "C22") (pin "1") (pintype "unspecified"))
      (node (ref "C5") (pin "1") (pinfunction "1_1") (pintype "input"))
      (node (ref "C6") (pin "2") (pinfunction "2_2") (pintype "unspecified"))
      (node (ref "C7") (pin "1") (pintype "unspecified"))
      (node (ref "D4") (pin "2") (pinfunction "2_2") (pintype "input"))
      (node (ref "H10") (pin "1") (pinfunction "1_1") (pintype "unspecified"))
      (node (ref "H2") (pin "2") (pinfunction "2_2") (pintype "unspecified"))
      (node (ref "H4") (pin "2") (pinfunction "2_2") (pintype "unspecified"))
      (node (ref "H6") (pin "2") (pinfunction "2_2") (pintype "unspecified"))
      (node (ref "H7") (pin "1") (pinfunction "1_1") (pintype "unspecified"))
      (node (ref "H7") (pin "3") (pinfunction "3_3") (pintype "unspecified"))
      (node (ref "H7") (pin "5") (pinfunction "5_5") (pintype "unspecified"))
      (node (ref "H8") (pin "1") (pinfunction "1_1") (pintype "unspecified"))
      (node (ref "H8") (pin "3") (pinfunction "3_3") (pintype "unspecified"))
      (node (ref "H8") (pin "5") (pinfunction "5_5") (pintype "unspecified"))
      (node (ref "H9") (pin "1") (pinfunction "1_1") (pintype "unspecified"))
      (node (ref "H9") (pin "3") (pinfunction "3_3") (pintype "unspecified"))
      (node (ref "H9") (pin "5") (pinfunction "5_5") (pintype "unspecified"))
      (node (ref "L1") (pin "1") (pinfunction "1_1") (pintype "unspecified"))
      (node (ref "P1") (pin "3") (pinfunction "3_3") (pintype "unspecified"))
      (node (ref "P19") (pin "1") (pinfunction "1_1") (pintype "unspecified"))
      (node (ref "P2") (pin "3") (pinfunction "3_3") (pintype "unspecified"))
      (node (ref "P20") (pin "1") (pinfunction "1_1") (pintype "unspecified"))
      (node (ref "P21") (pin "1") (pinfunction "1_1") (pintype "unspecified"))
      (node (ref "P21") (pin "2") (pinfunction "2_2") (pintype "unspecified"))
      (node (ref "P23") (pin "1") (pinfunction "1_1") (pintype "unspecified"))
      (node (ref "P3") (pin "3") (pinfunction "3_3") (pintype "unspecified"))
      (node (ref "R1") (pin "2") (pinfunction "2_2") (pintype "unspecified"))
      (node (ref "R11") (pin "1") (pinfunction "1_1") (pintype "unspecified"))
      (node (ref "R36") (pin "2") (pinfunction "2_2") (pintype "input"))
      (node (ref "R4") (pin "2") (pinfunction "2_2") (pintype "unspecified"))
      (node (ref "R6") (pin "2") (pinfunction "2_2") (pintype "unspecified"))
      (node (ref "R8") (pin "2") (pinfunction "2_2") (pintype "unspecified"))
      (node (ref "U1") (pin "3") (pinfunction "FB_3") (pintype "input"))
      (node (ref "U2") (pin "3") (pinfunction "IN_3") (pintype "unspecified"))
      (node (ref "U4") (pin "9") (pinfunction "COM_9") (pintype "unspecified"))
      (node (ref "U5") (pin "5") (pinfunction "VCC_5") (pintype "unspecified"))
      (node (ref "U6") (pin "5") (pinfunction "VCC_5") (pintype "unspecified"))
      (node (ref "U7") (pin "16") (pinfunction "VCC_16") (pintype "unspecified"))
    )
    (net (code "72") (name "24V") (class "Default")
      (node (ref "D1") (pin "1") (pinfunction "1_1") (pintype "unspecified"))
      (node (ref "DC1") (pin "1") (pinfunction "1_1") (pintype "unspecified"))
      (node (ref "P27") (pin "2") (pinfunction "2_2") (pintype "unspecified"))
      (node (ref "R3") (pin "2") (pinfunction "2_2") (pintype "unspecified"))
      (node (ref "R37") (pin "2") (pinfunction "2_2") (pintype "input"))
      (node (ref "R38") (pin "2") (pinfunction "2_2") (pintype "input"))
      (node (ref "R39") (pin "2") (pinfunction "2_2") (pintype "input"))
    )
    (net (code "73") (name "48V_SPN+") (class "Default")
      (node (ref "C20") (pin "1") (pintype "unspecified"))
      (node (ref "DZ1") (pin "2") (pinfunction "2_2") (pintype "input"))
      (node (ref "P11") (pin "1") (pinfunction "1_1") (pintype "unspecified"))
      (node (ref "P14") (pin "1") (pinfunction "1_1") (pintype "unspecified"))
      (node (ref "R34") (pin "2") (pinfunction "2_2") (pintype "input"))
    )
    (net (code "74") (name "GND") (class "Default")
      (node (ref "C1") (pin "1") (pinfunction "1_1") (pintype "unspecified"))
      (node (ref "C10") (pin "1") (pinfunction "1_1") (pintype "unspecified"))
      (node (ref "C11") (pin "1") (pinfunction "1_1") (pintype "unspecified"))
      (node (ref "C12") (pin "1") (pinfunction "1_1") (pintype "unspecified"))
      (node (ref "C13") (pin "1") (pinfunction "1_1") (pintype "unspecified"))
      (node (ref "C14") (pin "1") (pinfunction "1_1") (pintype "unspecified"))
      (node (ref "C15") (pin "1") (pinfunction "1_1") (pintype "unspecified"))
      (node (ref "C16") (pin "1") (pinfunction "1_1") (pintype "unspecified"))
      (node (ref "C17") (pin "2") (pintype "unspecified"))
      (node (ref "C18") (pin "2") (pintype "unspecified"))
      (node (ref "C19") (pin "2") (pintype "unspecified"))
      (node (ref "C2") (pin "2") (pintype "unspecified"))
      (node (ref "C21") (pin "2") (pinfunction "2_2") (pintype "unspecified"))
      (node (ref "C22") (pin "2") (pintype "unspecified"))
      (node (ref "C23") (pin "2") (pinfunction "2_2") (pintype "unspecified"))
      (node (ref "C24") (pin "2") (pinfunction "2_2") (pintype "unspecified"))
      (node (ref "C25") (pin "2") (pinfunction "2_2") (pintype "unspecified"))
      (node (ref "C26") (pin "1") (pinfunction "1_1") (pintype "unspecified"))
      (node (ref "C27") (pin "2") (pinfunction "2_2") (pintype "unspecified"))
      (node (ref "C3") (pin "1") (pinfunction "1_1") (pintype "unspecified"))
      (node (ref "C4") (pin "1") (pinfunction "1_1") (pintype "unspecified"))
      (node (ref "C5") (pin "2") (pinfunction "2_2") (pintype "input"))
      (node (ref "C6") (pin "1") (pinfunction "1_1") (pintype "unspecified"))
      (node (ref "C7") (pin "2") (pintype "unspecified"))
      (node (ref "C8") (pin "1") (pinfunction "1_1") (pintype "input"))
      (node (ref "C9") (pin "1") (pinfunction "1_1") (pintype "input"))
      (node (ref "D2") (pin "1") (pinfunction "1_1") (pintype "input"))
      (node (ref "D3") (pin "2") (pinfunction "2_2") (pintype "unspecified"))
      (node (ref "D4") (pin "1") (pinfunction "1_1") (pintype "input"))
      (node (ref "D5") (pin "2") (pinfunction "2_2") (pintype "unspecified"))
      (node (ref "D6") (pin "1") (pinfunction "1_1") (pintype "input"))
      (node (ref "D7") (pin "2") (pinfunction "2_2") (pintype "unspecified"))
      (node (ref "DC1") (pin "2") (pinfunction "2_2") (pintype "unspecified"))
      (node (ref "DC1") (pin "3") (pinfunction "3_3") (pintype "unspecified"))
      (node (ref "DZ2") (pin "1") (pinfunction "1_1") (pintype "input"))
      (node (ref "H2") (pin "1") (pinfunction "1_1") (pintype "unspecified"))
      (node (ref "H2") (pin "7") (pinfunction "7_7") (pintype "unspecified"))
      (node (ref "H4") (pin "1") (pinfunction "1_1") (pintype "unspecified"))
      (node (ref "H4") (pin "7") (pinfunction "7_7") (pintype "unspecified"))
      (node (ref "H6") (pin "1") (pinfunction "1_1") (pintype "unspecified"))
      (node (ref "H6") (pin "7") (pinfunction "7_7") (pintype "unspecified"))
      (node (ref "K1") (pin "1") (pinfunction "1_1") (pintype "unspecified"))
      (node (ref "K1") (pin "2") (pinfunction "2_2") (pintype "unspecified"))
      (node (ref "P1") (pin "2") (pinfunction "2_2") (pintype "unspecified"))
      (node (ref "P15") (pin "1") (pinfunction "1_1") (pintype "unspecified"))
      (node (ref "P16") (pin "1") (pinfunction "1_1") (pintype "input"))
      (node (ref "P17") (pin "1") (pinfunction "1_1") (pintype "input"))
      (node (ref "P18") (pin "1") (pinfunction "1_1") (pintype "input"))
      (node (ref "P19") (pin "3") (pinfunction "3_3") (pintype "unspecified"))
      (node (ref "P2") (pin "2") (pinfunction "2_2") (pintype "unspecified"))
      (node (ref "P20") (pin "3") (pinfunction "3_3") (pintype "unspecified"))
      (node (ref "P21") (pin "3") (pinfunction "3_3") (pintype "unspecified"))
      (node (ref "P21") (pin "4") (pinfunction "4_4") (pintype "unspecified"))
      (node (ref "P22") (pin "4") (pinfunction "GND_4") (pintype "unspecified"))
      (node (ref "P22") (pin "5") (pinfunction "GND_5") (pintype "unspecified"))
      (node (ref "P22") (pin "6") (pinfunction "GND_6") (pintype "unspecified"))
      (node (ref "P23") (pin "2") (pinfunction "2_2") (pintype "unspecified"))
      (node (ref "P24") (pin "1") (pinfunction "1_1") (pintype "unspecified"))
      (node (ref "P25") (pin "1") (pinfunction "1_1") (pintype "input"))
      (node (ref "P27") (pin "1") (pinfunction "1_1") (pintype "unspecified"))
      (node (ref "P3") (pin "2") (pinfunction "2_2") (pintype "unspecified"))
      (node (ref "P4") (pin "2") (pintype "input"))
      (node (ref "P5") (pin "2") (pintype "input"))
      (node (ref "P6") (pin "2") (pintype "input"))
      (node (ref "P7") (pin "2") (pintype "input"))
      (node (ref "P8") (pin "2") (pintype "input"))
      (node (ref "Q2") (pin "3") (pinfunction "E_3") (pintype "input"))
      (node (ref "R21") (pin "2") (pinfunction "2_2") (pintype "unspecified"))
      (node (ref "R22") (pin "2") (pinfunction "2_2") (pintype "unspecified"))
      (node (ref "R23") (pin "2") (pinfunction "2_2") (pintype "unspecified"))
      (node (ref "R24") (pin "2") (pinfunction "2_2") (pintype "unspecified"))
      (node (ref "R25") (pin "2") (pinfunction "2_2") (pintype "unspecified"))
      (node (ref "R26") (pin "2") (pinfunction "2_2") (pintype "unspecified"))
      (node (ref "R27") (pin "2") (pinfunction "2_2") (pintype "unspecified"))
      (node (ref "R28") (pin "2") (pinfunction "2_2") (pintype "unspecified"))
      (node (ref "R29") (pin "2") (pinfunction "2_2") (pintype "unspecified"))
      (node (ref "R30") (pin "2") (pinfunction "2_2") (pintype "unspecified"))
      (node (ref "R31") (pin "2") (pinfunction "2_2") (pintype "unspecified"))
      (node (ref "R32") (pin "2") (pinfunction "2_2") (pintype "unspecified"))
      (node (ref "R42") (pin "2") (pinfunction "2_2") (pintype "input"))
      (node (ref "R45") (pin "2") (pinfunction "2_2") (pintype "unspecified"))
      (node (ref "R46") (pin "2") (pinfunction "2_2") (pintype "unspecified"))
      (node (ref "R47") (pin "2") (pinfunction "2_2") (pintype "unspecified"))
      (node (ref "R49") (pin "2") (pinfunction "2_2") (pintype "input"))
      (node (ref "R50") (pin "2") (pinfunction "2_2") (pintype "unspecified"))
      (node (ref "R51") (pin "2") (pinfunction "2_2") (pintype "unspecified"))
      (node (ref "R52") (pin "2") (pinfunction "2_2") (pintype "unspecified"))
      (node (ref "R53") (pin "2") (pinfunction "2_2") (pintype "unspecified"))
      (node (ref "R54") (pin "2") (pinfunction "2_2") (pintype "unspecified"))
      (node (ref "R55") (pin "2") (pinfunction "2_2") (pintype "unspecified"))
      (node (ref "R56") (pin "1") (pinfunction "1_1") (pintype "input"))
      (node (ref "R57") (pin "1") (pinfunction "1_1") (pintype "input"))
      (node (ref "R58") (pin "2") (pinfunction "2_2") (pintype "input"))
      (node (ref "R7") (pin "2") (pinfunction "2_2") (pintype "unspecified"))
      (node (ref "U1") (pin "5") (pinfunction "GND_5") (pintype "input"))
      (node (ref "U1") (pin "6") (pinfunction "GND_6") (pintype "input"))
      (node (ref "U1") (pin "7") (pinfunction "GND_7") (pintype "input"))
      (node (ref "U1") (pin "8") (pinfunction "GND_8") (pintype "input"))
      (node (ref "U2") (pin "1") (pinfunction "GND_1") (pintype "unspecified"))
      (node (ref "U3") (pin "1") (pinfunction "GND_1") (pintype "unspecified"))
      (node (ref "U3") (pin "15") (pinfunction "GND_15") (pintype "unspecified"))
      (node (ref "U3") (pin "38") (pinfunction "GND_38") (pintype "unspecified"))
      (node (ref "U3") (pin "39") (pinfunction "EP_39") (pintype "unspecified"))
      (node (ref "U4") (pin "8") (pinfunction "GND_8") (pintype "unspecified"))
      (node (ref "U5") (pin "3") (pinfunction "GND_3") (pintype "unspecified"))
      (node (ref "U6") (pin "3") (pinfunction "GND_3") (pintype "unspecified"))
      (node (ref "U7") (pin "1") (pinfunction "GND_1") (pintype "unspecified"))
      (node (ref "U8") (pin "10") (pinfunction "GND_10") (pintype "unspecified"))
      (node (ref "U8") (pin "11") (pinfunction "GND_11") (pintype "unspecified"))
      (node (ref "U8") (pin "12") (pinfunction "GND_12") (pintype "unspecified"))
      (node (ref "U8") (pin "13") (pinfunction "GND_13") (pintype "unspecified"))
      (node (ref "U8") (pin "6") (pinfunction "VSS_6") (pintype "unspecified"))
      (node (ref "U9") (pin "2") (pinfunction "2_2") (pintype "unspecified"))
    )
    (net (code "75") (name "Net-(C12-Pad2)") (class "Default")
      (node (ref "C12") (pin "2") (pinfunction "2_2") (pintype "unspecified"))
      (node (ref "P4") (pin "1") (pintype "input"))
      (node (ref "R11") (pin "2") (pinfunction "2_2") (pintype "unspecified"))
      (node (ref "R12") (pin "2") (pinfunction "2_2") (pintype "input"))
    )
    (net (code "76") (name "Net-(C13-Pad2)") (class "Default")
      (node (ref "C13") (pin "2") (pinfunction "2_2") (pintype "unspecified"))
      (node (ref "P5") (pin "1") (pintype "input"))
      (node (ref "R13") (pin "2") (pinfunction "2_2") (pintype "unspecified"))
      (node (ref "R14") (pin "2") (pinfunction "2_2") (pintype "input"))
    )
    (net (code "77") (name "Net-(C14-Pad2)") (class "Default")
      (node (ref "C14") (pin "2") (pinfunction "2_2") (pintype "unspecified"))
      (node (ref "K1") (pin "3") (pinfunction "3_3") (pintype "unspecified"))
      (node (ref "K1") (pin "4") (pinfunction "4_4") (pintype "unspecified"))
      (node (ref "P7") (pin "1") (pintype "input"))
      (node (ref "R15") (pin "2") (pinfunction "2_2") (pintype "unspecified"))
      (node (ref "R18") (pin "2") (pinfunction "2_2") (pintype "input"))
    )
    (net (code "78") (name "Net-(C15-Pad2)") (class "Default")
      (node (ref "C15") (pin "2") (pinfunction "2_2") (pintype "unspecified"))
      (node (ref "P8") (pin "1") (pintype "input"))
      (node (ref "R16") (pin "2") (pinfunction "2_2") (pintype "unspecified"))
      (node (ref "R19") (pin "2") (pinfunction "2_2") (pintype "input"))
    )
    (net (code "79") (name "Net-(C16-Pad2)") (class "Default")
      (node (ref "C16") (pin "2") (pinfunction "2_2") (pintype "unspecified"))
      (node (ref "P6") (pin "1") (pintype "input"))
      (node (ref "R17") (pin "2") (pinfunction "2_2") (pintype "unspecified"))
      (node (ref "R20") (pin "2") (pinfunction "2_2") (pintype "input"))
    )
    (net (code "80") (name "Net-(D3-Pad1)") (class "Default")
      (node (ref "D3") (pin "1") (pinfunction "1_1") (pintype "unspecified"))
      (node (ref "R3") (pin "1") (pinfunction "1_1") (pintype "unspecified"))
    )
    (net (code "81") (name "Net-(D5-Pad1)") (class "Default")
      (node (ref "D5") (pin "1") (pinfunction "1_1") (pintype "unspecified"))
      (node (ref "R6") (pin "1") (pinfunction "1_1") (pintype "unspecified"))
    )
    (net (code "82") (name "Net-(D7-Pad1)") (class "Default")
      (node (ref "D7") (pin "1") (pinfunction "1_1") (pintype "unspecified"))
      (node (ref "R10") (pin "1") (pinfunction "1_1") (pintype "unspecified"))
    )
    (net (code "83") (name "Net-(D8-Pad1)") (class "Default")
      (node (ref "D8") (pin "1") (pinfunction "1_1") (pintype "unspecified"))
      (node (ref "R34") (pin "1") (pinfunction "1_1") (pintype "input"))
    )
    (net (code "84") (name "Net-(D10-Pad2)") (class "Default")
      (node (ref "D10") (pin "2") (pinfunction "2_2") (pintype "unspecified"))
      (node (ref "H10") (pin "2") (pinfunction "2_2") (pintype "unspecified"))
    )
    (net (code "85") (name "Net-(H1-Pad3)") (class "Default")
      (node (ref "H1") (pin "3") (pinfunction "3_3") (pintype "unspecified"))
      (node (ref "H1") (pin "4") (pinfunction "4_4") (pintype "unspecified"))
    )
    (net (code "86") (name "Net-(H3-Pad3)") (class "Default")
      (node (ref "H3") (pin "3") (pinfunction "3_3") (pintype "unspecified"))
      (node (ref "H3") (pin "4") (pinfunction "4_4") (pintype "unspecified"))
    )
    (net (code "87") (name "Net-(H5-Pad3)") (class "Default")
      (node (ref "H5") (pin "3") (pinfunction "3_3") (pintype "unspecified"))
      (node (ref "H5") (pin "4") (pinfunction "4_4") (pintype "unspecified"))
    )
    (net (code "88") (name "Net-(P21-Pad6)") (class "Default")
      (node (ref "P21") (pin "6") (pinfunction "6_6") (pintype "unspecified"))
      (node (ref "P23") (pin "3") (pinfunction "3_3") (pintype "unspecified"))
      (node (ref "R65") (pin "2") (pinfunction "2_2") (pintype "unspecified"))
    )
    (net (code "89") (name "Net-(P21-Pad8)") (class "Default")
      (node (ref "P21") (pin "8") (pinfunction "8_8") (pintype "unspecified"))
      (node (ref "P23") (pin "4") (pinfunction "4_4") (pintype "unspecified"))
      (node (ref "R67") (pin "2") (pinfunction "2_2") (pintype "unspecified"))
    )
    (net (code "90") (name "Net-(Q1-D)") (class "Default")
      (node (ref "D8") (pin "2") (pinfunction "2_2") (pintype "unspecified"))
      (node (ref "D9") (pin "2") (pinfunction "2_2") (pintype "input"))
      (node (ref "DZ1") (pin "1") (pinfunction "1_1") (pintype "input"))
      (node (ref "P14") (pin "2") (pinfunction "2_2") (pintype "unspecified"))
      (node (ref "Q1") (pin "2") (pinfunction "D_2") (pintype "unspecified"))
      (node (ref "Q3") (pin "4") (pinfunction "D_4") (pintype "unspecified"))
    )
    (net (code "91") (name "Net-(Q2-B)") (class "Default")
      (node (ref "Q2") (pin "1") (pinfunction "B_1") (pintype "input"))
      (node (ref "R36") (pin "1") (pinfunction "1_1") (pintype "input"))
      (node (ref "R43") (pin "2") (pinfunction "2_2") (pintype "input"))
    )
    (net (code "92") (name "Net-(Q4-B)") (class "Default")
      (node (ref "Q4") (pin "1") (pinfunction "B_1") (pintype "unspecified"))
      (node (ref "R62") (pin "2") (pinfunction "2_2") (pintype "unspecified"))
    )
    (net (code "93") (name "Net-(Q4-E)") (class "Default")
      (node (ref "Q4") (pin "2") (pinfunction "E_2") (pintype "unspecified"))
      (node (ref "R69") (pin "1") (pinfunction "1_1") (pintype "unspecified"))
      (node (ref "U7") (pin "13") (pinfunction "DTR#_13") (pintype "unspecified"))
    )
    (net (code "94") (name "Net-(Q5-B)") (class "Default")
      (node (ref "Q5") (pin "1") (pinfunction "B_1") (pintype "unspecified"))
      (node (ref "R69") (pin "2") (pinfunction "2_2") (pintype "unspecified"))
    )
    (net (code "95") (name "Net-(Q5-E)") (class "Default")
      (node (ref "Q5") (pin "2") (pinfunction "E_2") (pintype "unspecified"))
      (node (ref "R62") (pin "1") (pinfunction "1_1") (pintype "unspecified"))
      (node (ref "U7") (pin "14") (pinfunction "RTS#_14") (pintype "unspecified"))
    )
    (net (code "96") (name "Net-(U1-ON{slash}OFF)") (class "Default")
      (node (ref "R7") (pin "1") (pinfunction "1_1") (pintype "unspecified"))
      (node (ref "U1") (pin "4") (pinfunction "ON/OFF_4") (pintype "input"))
    )
    (net (code "97") (name "Net-(U1-OUTPUT)") (class "Default")
      (node (ref "D2") (pin "2") (pinfunction "2_2") (pintype "input"))
      (node (ref "L1") (pin "2") (pinfunction "2_2") (pintype "unspecified"))
      (node (ref "U1") (pin "2") (pinfunction "OUTPUT_2") (pintype "input"))
    )
    (net (code "98") (name "Net-(U5-A)") (class "Default")
      (node (ref "R40") (pin "2") (pinfunction "2_2") (pintype "input"))
      (node (ref "R41") (pin "2") (pinfunction "2_2") (pintype "input"))
      (node (ref "R42") (pin "1") (pinfunction "1_1") (pintype "input"))
      (node (ref "U5") (pin "2") (pinfunction "A_2") (pintype "unspecified"))
    )
    (net (code "99") (name "Net-(U5-Y)") (class "Default")
      (node (ref "R43") (pin "1") (pinfunction "1_1") (pintype "input"))
      (node (ref "R48") (pin "2") (pinfunction "2_2") (pintype "input"))
      (node (ref "U5") (pin "4") (pinfunction "Y_4") (pintype "unspecified"))
    )
    (net (code "100") (name "Net-(U6-Y)") (class "Default")
      (node (ref "R59") (pin "1") (pinfunction "1_1") (pintype "input"))
      (node (ref "U6") (pin "4") (pinfunction "Y_4") (pintype "unspecified"))
    )
    (net (code "101") (name "Net-(U7-RXD)") (class "Default")
      (node (ref "R61") (pin "1") (pinfunction "1_1") (pintype "unspecified"))
      (node (ref "U7") (pin "3") (pinfunction "RXD_3") (pintype "unspecified"))
    )
    (net (code "102") (name "Net-(U7-TXD)") (class "Default")
      (node (ref "R60") (pin "1") (pinfunction "1_1") (pintype "unspecified"))
      (node (ref "U7") (pin "2") (pinfunction "TXD_2") (pintype "unspecified"))
    )
    (net (code "103") (name "Net-(U7-UD+)") (class "Default")
      (node (ref "U7") (pin "5") (pinfunction "UD+_5") (pintype "unspecified"))
      (node (ref "U9") (pin "6") (pinfunction "6_6") (pintype "unspecified"))
    )
    (net (code "104") (name "Net-(U7-UD-)") (class "Default")
      (node (ref "U7") (pin "6") (pinfunction "UD-_6") (pintype "unspecified"))
      (node (ref "U9") (pin "4") (pinfunction "4_4") (pintype "unspecified"))
    )
    (net (code "105") (name "Net-(U7-V3)") (class "Default")
      (node (ref "C23") (pin "1") (pinfunction "1_1") (pintype "unspecified"))
      (node (ref "U7") (pin "4") (pinfunction "V3_4") (pintype "unspecified"))
    )
    (net (code "106") (name "Net-(U7-XI)") (class "Default")
      (node (ref "C24") (pin "1") (pinfunction "1_1") (pintype "unspecified"))
      (node (ref "U7") (pin "7") (pinfunction "XI_7") (pintype "unspecified"))
      (node (ref "Y1") (pin "2") (pinfunction "OSC2_2") (pintype "unspecified"))
    )
    (net (code "107") (name "Net-(U7-XO)") (class "Default")
      (node (ref "C25") (pin "1") (pinfunction "1_1") (pintype "unspecified"))
      (node (ref "U7") (pin "8") (pinfunction "XO_8") (pintype "unspecified"))
      (node (ref "Y1") (pin "1") (pinfunction "OSC1_1") (pintype "unspecified"))
    )
    (net (code "108") (name "VIN_24V") (class "Default")
      (node (ref "C2") (pin "1") (pintype "unspecified"))
      (node (ref "C3") (pin "2") (pinfunction "2_2") (pintype "unspecified"))
      (node (ref "D1") (pin "2") (pinfunction "2_2") (pintype "unspecified"))
      (node (ref "U1") (pin "1") (pinfunction "VIN_1") (pintype "input"))
    )
    (net (code "109") (name "VUSB") (class "Default")
      (node (ref "D10") (pin "1") (pinfunction "1_1") (pintype "unspecified"))
      (node (ref "P22") (pin "1") (pinfunction "VBUS_1") (pintype "unspecified"))
      (node (ref "U9") (pin "5") (pinfunction "5_5") (pintype "unspecified"))
    )
    (net (code "110") (name "unconnected-(P21-Pad7)") (class "Default")
      (node (ref "P21") (pin "7") (pinfunction "7_7") (pintype "unspecified"))
    )
    (net (code "111") (name "unconnected-(U3-CLK-Pad20)") (class "Default")
      (node (ref "U3") (pin "20") (pinfunction "CLK_20") (pintype "unspecified"))
    )
    (net (code "112") (name "unconnected-(U3-CMD-Pad19)") (class "Default")
      (node (ref "U3") (pin "19") (pinfunction "CMD_19") (pintype "unspecified"))
    )
    (net (code "113") (name "unconnected-(U3-NC-Pad32)") (class "Default")
      (node (ref "U3") (pin "32") (pinfunction "NC_32") (pintype "unspecified"))
    )
    (net (code "114") (name "unconnected-(U3-SD0-Pad21)") (class "Default")
      (node (ref "U3") (pin "21") (pinfunction "SD0_21") (pintype "unspecified"))
    )
    (net (code "115") (name "unconnected-(U3-SD1-Pad22)") (class "Default")
      (node (ref "U3") (pin "22") (pinfunction "SD1_22") (pintype "unspecified"))
    )
    (net (code "116") (name "unconnected-(U3-SD2-Pad17)") (class "Default")
      (node (ref "U3") (pin "17") (pinfunction "SD2_17") (pintype "unspecified"))
    )
    (net (code "117") (name "unconnected-(U3-SD3-Pad18)") (class "Default")
      (node (ref "U3") (pin "18") (pinfunction "SD3_18") (pintype "unspecified"))
    )
    (net (code "118") (name "unconnected-(U5-NC-Pad1)") (class "Default")
      (node (ref "U5") (pin "1") (pinfunction "NC_1") (pintype "unspecified"))
    )
    (net (code "119") (name "unconnected-(U6-NC-Pad1)") (class "Default")
      (node (ref "U6") (pin "1") (pinfunction "NC_1") (pintype "unspecified"))
    )
    (net (code "120") (name "unconnected-(U7-CTS#-Pad9)") (class "Default")
      (node (ref "U7") (pin "9") (pinfunction "CTS#_9") (pintype "unspecified"))
    )
    (net (code "121") (name "unconnected-(U7-DCD#-Pad12)") (class "Default")
      (node (ref "U7") (pin "12") (pinfunction "DCD#_12") (pintype "unspecified"))
    )
    (net (code "122") (name "unconnected-(U7-DSR#-Pad10)") (class "Default")
      (node (ref "U7") (pin "10") (pinfunction "DSR#_10") (pintype "unspecified"))
    )
    (net (code "123") (name "unconnected-(U7-R232-Pad15)") (class "Default")
      (node (ref "U7") (pin "15") (pinfunction "R232_15") (pintype "unspecified"))
    )
    (net (code "124") (name "unconnected-(U7-RI#-Pad11)") (class "Default")
      (node (ref "U7") (pin "11") (pinfunction "RI#_11") (pintype "unspecified"))
    )
    (net (code "125") (name "unconnected-(U8-DAT1-Pad8)") (class "Default")
      (node (ref "U8") (pin "8") (pinfunction "DAT1_8") (pintype "unspecified"))
    )
    (net (code "126") (name "unconnected-(U8-DAT2-Pad1)") (class "Default")
      (node (ref "U8") (pin "1") (pinfunction "DAT2_1") (pintype "unspecified"))
    )
  )
)
